# Adafruit_Trellis_4x4_3mm_HT16K33.net
KiCad netlist of a schematic drawn in EAGLE
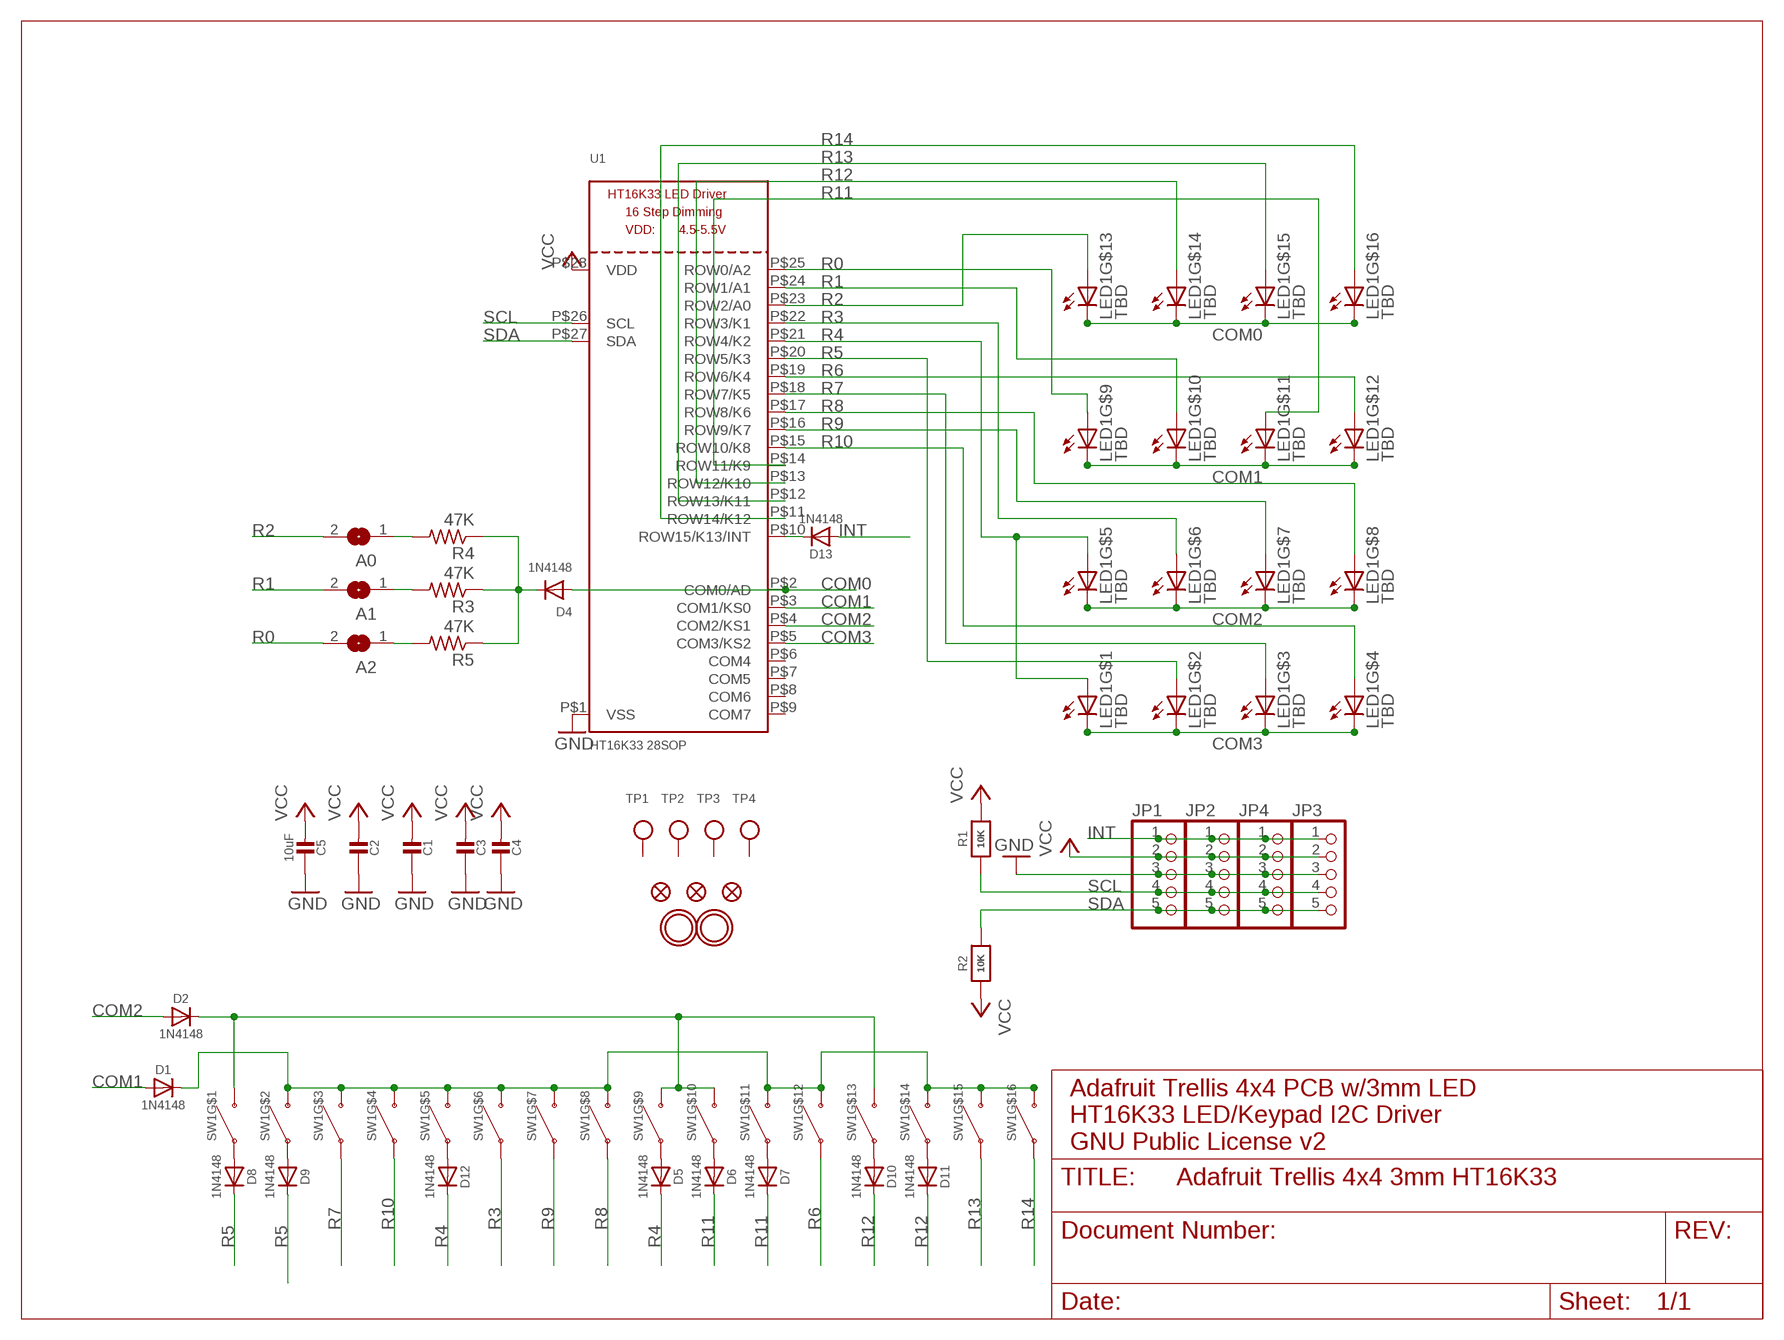
[diagram p0: schematic, sheet 1]

(export (version "E")
  (design (tool "Eeschema 10.0.6"))
  (components
    (comp (ref "A0")
      (value "SOLDERJUMPERREFLOW_NOPASTE")
      (footprint "eagle-import:SOLDERJUMPER_REFLOW_NOPASTE")
      (libsource (lib "eagle-import") (part "SOLDERJUMPERREFLOW_NOPASTE"))
    )
    (comp (ref "A1")
      (value "SOLDERJUMPERREFLOW_NOPASTE")
      (footprint "eagle-import:SOLDERJUMPER_REFLOW_NOPASTE")
      (libsource (lib "eagle-import") (part "SOLDERJUMPERREFLOW_NOPASTE"))
    )
    (comp (ref "A2")
      (value "SOLDERJUMPERREFLOW_NOPASTE")
      (footprint "eagle-import:SOLDERJUMPER_REFLOW_NOPASTE")
      (libsource (lib "eagle-import") (part "SOLDERJUMPERREFLOW_NOPASTE"))
    )
    (comp (ref "C1")
      (value "CAP_CERAMIC_0805")
      (footprint "eagle-import:_0805")
      (libsource (lib "eagle-import") (part "CAP_CERAMIC_0805"))
    )
    (comp (ref "C2")
      (value "CAP_CERAMIC_0805")
      (footprint "eagle-import:_0805")
      (libsource (lib "eagle-import") (part "CAP_CERAMIC_0805"))
    )
    (comp (ref "C3")
      (value "CAP_CERAMIC_0805")
      (footprint "eagle-import:_0805")
      (libsource (lib "eagle-import") (part "CAP_CERAMIC_0805"))
    )
    (comp (ref "C4")
      (value "CAP_CERAMIC_0805")
      (footprint "eagle-import:_0805")
      (libsource (lib "eagle-import") (part "CAP_CERAMIC_0805"))
    )
    (comp (ref "C5")
      (value "10uF")
      (footprint "eagle-import:_0805")
      (libsource (lib "eagle-import") (part "CAP_CERAMIC_0805"))
    )
    (comp (ref "D1")
      (value "1N4148")
      (footprint "eagle-import:SOD-323")
      (libsource (lib "eagle-import") (part "DIODESOD-323"))
    )
    (comp (ref "D2")
      (value "1N4148")
      (footprint "eagle-import:SOD-323")
      (libsource (lib "eagle-import") (part "DIODESOD-323"))
    )
    (comp (ref "D4")
      (value "1N4148")
      (footprint "eagle-import:SOD-323F")
      (libsource (lib "eagle-import") (part "DIODESOD-323F"))
    )
    (comp (ref "D5")
      (value "1N4148")
      (footprint "eagle-import:SOD-323")
      (libsource (lib "eagle-import") (part "DIODESOD-323"))
    )
    (comp (ref "D6")
      (value "1N4148")
      (footprint "eagle-import:SOD-323")
      (libsource (lib "eagle-import") (part "DIODESOD-323"))
    )
    (comp (ref "D7")
      (value "1N4148")
      (footprint "eagle-import:SOD-323")
      (libsource (lib "eagle-import") (part "DIODESOD-323"))
    )
    (comp (ref "D8")
      (value "1N4148")
      (footprint "eagle-import:SOD-323")
      (libsource (lib "eagle-import") (part "DIODESOD-323"))
    )
    (comp (ref "D9")
      (value "1N4148")
      (footprint "eagle-import:SOD-323")
      (libsource (lib "eagle-import") (part "DIODESOD-323"))
    )
    (comp (ref "D10")
      (value "1N4148")
      (footprint "eagle-import:SOD-323")
      (libsource (lib "eagle-import") (part "DIODESOD-323"))
    )
    (comp (ref "D11")
      (value "1N4148")
      (footprint "eagle-import:SOD-323")
      (libsource (lib "eagle-import") (part "DIODESOD-323"))
    )
    (comp (ref "D12")
      (value "1N4148")
      (footprint "eagle-import:SOD-323")
      (libsource (lib "eagle-import") (part "DIODESOD-323"))
    )
    (comp (ref "D13")
      (value "1N4148")
      (footprint "eagle-import:SOD-323")
      (libsource (lib "eagle-import") (part "DIODESOD-323"))
    )
    (comp (ref "FID1")
      (value "FIDUCIAL\"\"")
      (footprint "eagle-import:FIDUCIAL_1MM")
      (libsource (lib "eagle-import") (part "FIDUCIAL{dblquote}{dblquote}"))
    )
    (comp (ref "FID2")
      (value "FIDUCIAL\"\"")
      (footprint "eagle-import:FIDUCIAL_1MM")
      (libsource (lib "eagle-import") (part "FIDUCIAL{dblquote}{dblquote}"))
    )
    (comp (ref "FID3")
      (value "FIDUCIAL\"\"")
      (footprint "eagle-import:FIDUCIAL_1MM")
      (libsource (lib "eagle-import") (part "FIDUCIAL{dblquote}{dblquote}"))
    )
    (comp (ref "JP1")
      (value "HEADER-1X5EDGESMT")
      (footprint "eagle-import:1X5_SMT")
      (libsource (lib "eagle-import") (part "HEADER-1X5EDGESMT"))
    )
    (comp (ref "JP2")
      (value "HEADER-1X5EDGESMT")
      (footprint "eagle-import:1X5_SMT")
      (libsource (lib "eagle-import") (part "HEADER-1X5EDGESMT"))
    )
    (comp (ref "JP3")
      (value "HEADER-1X5EDGESMT")
      (footprint "eagle-import:1X5_SMT")
      (libsource (lib "eagle-import") (part "HEADER-1X5EDGESMT"))
    )
    (comp (ref "JP4")
      (value "HEADER-1X5EDGESMT")
      (footprint "eagle-import:1X5_SMT")
      (libsource (lib "eagle-import") (part "HEADER-1X5EDGESMT"))
    )
    (comp (ref "LED1")
      (value "TBD")
      (footprint "eagle-import:LED3MM-4X4GRID")
      (libsource (lib "eagle-import") (part "LED-3MM-4X4GRID-3MM"))
    )
    (comp (ref "R1")
      (value "10K")
      (footprint "eagle-import:_0805")
      (libsource (lib "eagle-import") (part "RESISTOR_0805"))
    )
    (comp (ref "R2")
      (value "10K")
      (footprint "eagle-import:_0805")
      (libsource (lib "eagle-import") (part "RESISTOR_0805"))
    )
    (comp (ref "R3")
      (value "47K")
      (footprint "eagle-import:R0805")
      (libsource (lib "eagle-import") (part "R-US_R0805"))
    )
    (comp (ref "R4")
      (value "47K")
      (footprint "eagle-import:R0805")
      (libsource (lib "eagle-import") (part "R-US_R0805"))
    )
    (comp (ref "R5")
      (value "47K")
      (footprint "eagle-import:R0805")
      (libsource (lib "eagle-import") (part "R-US_R0805"))
    )
    (comp (ref "SW1")
      (value "SWITCH-SILICON-4X4GRID-10MM-5.4MM")
      (footprint "eagle-import:ELAST_PAD_SQUARE_10MM_5.4MM_4X4GRID")
      (libsource (lib "eagle-import") (part "SWITCH-SILICON-4X4GRID-10MM-5.4MM"))
    )
    (comp (ref "TP1")
      (value "TESTPOINT")
      (footprint "eagle-import:TESTPOINT_SMT")
      (libsource (lib "eagle-import") (part "TESTPOINT"))
    )
    (comp (ref "TP2")
      (value "TESTPOINT")
      (footprint "eagle-import:TESTPOINT_SMT")
      (libsource (lib "eagle-import") (part "TESTPOINT"))
    )
    (comp (ref "TP3")
      (value "TESTPOINT")
      (footprint "eagle-import:TESTPOINT_SMT")
      (libsource (lib "eagle-import") (part "TESTPOINT"))
    )
    (comp (ref "TP4")
      (value "TESTPOINT")
      (footprint "eagle-import:TESTPOINT_SMT")
      (libsource (lib "eagle-import") (part "TESTPOINT"))
    )
    (comp (ref "U$1")
      (value "MOUNTINGHOLE2.5")
      (footprint "eagle-import:MOUNTINGHOLE_2.5_PLATED")
      (libsource (lib "eagle-import") (part "MOUNTINGHOLE2.5"))
    )
    (comp (ref "U$2")
      (value "MOUNTINGHOLE2.5")
      (footprint "eagle-import:MOUNTINGHOLE_2.5_PLATED")
      (libsource (lib "eagle-import") (part "MOUNTINGHOLE2.5"))
    )
    (comp (ref "U1")
      (value "HT16K33 28SOP")
      (footprint "eagle-import:SOP28_300MIL")
      (libsource (lib "eagle-import") (part "HT16K33_SOP28"))
    )
  )
  (nets
    (net (code "1") (name "/COM0") (class "Default")
      (node (ref "D4") (pin "A") (pinfunction "A_A") (pintype "passive"))
      (node (ref "LED1") (pin "K13") (pinfunction "C_K13") (pintype "passive"))
      (node (ref "LED1") (pin "K14") (pinfunction "C_K14") (pintype "passive"))
      (node (ref "LED1") (pin "K15") (pinfunction "C_K15") (pintype "passive"))
      (node (ref "LED1") (pin "K16") (pinfunction "C_K16") (pintype "passive"))
      (node (ref "U1") (pin "P$2") (pinfunction "COM0/AD_P$2") (pintype "bidirectional"))
    )
    (net (code "2") (name "/COM1") (class "Default")
      (node (ref "D1") (pin "A") (pinfunction "A_A") (pintype "passive"))
      (node (ref "LED1") (pin "K10") (pinfunction "C_K10") (pintype "passive"))
      (node (ref "LED1") (pin "K11") (pinfunction "C_K11") (pintype "passive"))
      (node (ref "LED1") (pin "K12") (pinfunction "C_K12") (pintype "passive"))
      (node (ref "LED1") (pin "K9") (pinfunction "C_K9") (pintype "passive"))
      (node (ref "U1") (pin "P$3") (pinfunction "COM1/KS0_P$3") (pintype "bidirectional"))
    )
    (net (code "3") (name "/COM2") (class "Default")
      (node (ref "D2") (pin "A") (pinfunction "A_A") (pintype "passive"))
      (node (ref "LED1") (pin "K5") (pinfunction "C_K5") (pintype "passive"))
      (node (ref "LED1") (pin "K6") (pinfunction "C_K6") (pintype "passive"))
      (node (ref "LED1") (pin "K7") (pinfunction "C_K7") (pintype "passive"))
      (node (ref "LED1") (pin "K8") (pinfunction "C_K8") (pintype "passive"))
      (node (ref "U1") (pin "P$4") (pinfunction "COM2/KS1_P$4") (pintype "bidirectional"))
    )
    (net (code "4") (name "/COM3") (class "Default")
      (node (ref "LED1") (pin "K1") (pinfunction "C_K1") (pintype "passive"))
      (node (ref "LED1") (pin "K2") (pinfunction "C_K2") (pintype "passive"))
      (node (ref "LED1") (pin "K3") (pinfunction "C_K3") (pintype "passive"))
      (node (ref "LED1") (pin "K4") (pinfunction "C_K4") (pintype "passive"))
      (node (ref "U1") (pin "P$5") (pinfunction "COM3/KS2_P$5") (pintype "bidirectional"))
    )
    (net (code "5") (name "/INT") (class "Default")
      (node (ref "D13") (pin "A") (pinfunction "A_A") (pintype "passive"))
      (node (ref "JP1") (pin "1") (pinfunction "1_1") (pintype "passive"))
      (node (ref "JP2") (pin "1") (pinfunction "1_1") (pintype "passive"))
      (node (ref "JP3") (pin "1") (pinfunction "1_1") (pintype "passive"))
      (node (ref "JP4") (pin "1") (pinfunction "1_1") (pintype "passive"))
    )
    (net (code "6") (name "/R0") (class "Default")
      (node (ref "A2") (pin "2") (pinfunction "2_2") (pintype "passive"))
      (node (ref "LED1") (pin "A9") (pinfunction "A_A9") (pintype "passive"))
      (node (ref "U1") (pin "P$25") (pinfunction "ROW0/A2_P$25") (pintype "bidirectional"))
    )
    (net (code "7") (name "/R1") (class "Default")
      (node (ref "A1") (pin "2") (pinfunction "2_2") (pintype "passive"))
      (node (ref "LED1") (pin "A10") (pinfunction "A_A10") (pintype "passive"))
      (node (ref "U1") (pin "P$24") (pinfunction "ROW1/A1_P$24") (pintype "bidirectional"))
    )
    (net (code "8") (name "/R2") (class "Default")
      (node (ref "A0") (pin "2") (pinfunction "2_2") (pintype "passive"))
      (node (ref "LED1") (pin "A13") (pinfunction "A_A13") (pintype "passive"))
      (node (ref "U1") (pin "P$23") (pinfunction "ROW2/A0_P$23") (pintype "bidirectional"))
    )
    (net (code "9") (name "/R3") (class "Default")
      (node (ref "LED1") (pin "A6") (pinfunction "A_A6") (pintype "passive"))
      (node (ref "SW1") (pin "A6") (pinfunction "P$1_A6") (pintype "bidirectional"))
      (node (ref "U1") (pin "P$22") (pinfunction "ROW3/K1_P$22") (pintype "bidirectional"))
    )
    (net (code "10") (name "/R4") (class "Default")
      (node (ref "D12") (pin "C") (pinfunction "C_C") (pintype "passive"))
      (node (ref "D5") (pin "C") (pinfunction "C_C") (pintype "passive"))
      (node (ref "LED1") (pin "A1") (pinfunction "A_A1") (pintype "passive"))
      (node (ref "LED1") (pin "A5") (pinfunction "A_A5") (pintype "passive"))
      (node (ref "U1") (pin "P$21") (pinfunction "ROW4/K2_P$21") (pintype "bidirectional"))
    )
    (net (code "11") (name "/R5") (class "Default")
      (node (ref "D8") (pin "C") (pinfunction "C_C") (pintype "passive"))
      (node (ref "D9") (pin "C") (pinfunction "C_C") (pintype "passive"))
      (node (ref "LED1") (pin "A2") (pinfunction "A_A2") (pintype "passive"))
      (node (ref "U1") (pin "P$20") (pinfunction "ROW5/K3_P$20") (pintype "bidirectional"))
    )
    (net (code "12") (name "/R6") (class "Default")
      (node (ref "LED1") (pin "A12") (pinfunction "A_A12") (pintype "passive"))
      (node (ref "SW1") (pin "A12") (pinfunction "P$1_A12") (pintype "bidirectional"))
      (node (ref "U1") (pin "P$19") (pinfunction "ROW6/K4_P$19") (pintype "bidirectional"))
    )
    (net (code "13") (name "/R7") (class "Default")
      (node (ref "LED1") (pin "A3") (pinfunction "A_A3") (pintype "passive"))
      (node (ref "SW1") (pin "A3") (pinfunction "P$1_A3") (pintype "bidirectional"))
      (node (ref "U1") (pin "P$18") (pinfunction "ROW7/K5_P$18") (pintype "bidirectional"))
    )
    (net (code "14") (name "/R8") (class "Default")
      (node (ref "LED1") (pin "A8") (pinfunction "A_A8") (pintype "passive"))
      (node (ref "SW1") (pin "A8") (pinfunction "P$1_A8") (pintype "bidirectional"))
      (node (ref "U1") (pin "P$17") (pinfunction "ROW8/K6_P$17") (pintype "bidirectional"))
    )
    (net (code "15") (name "/R9") (class "Default")
      (node (ref "LED1") (pin "A7") (pinfunction "A_A7") (pintype "passive"))
      (node (ref "SW1") (pin "A7") (pinfunction "P$1_A7") (pintype "bidirectional"))
      (node (ref "U1") (pin "P$16") (pinfunction "ROW9/K7_P$16") (pintype "bidirectional"))
    )
    (net (code "16") (name "/R10") (class "Default")
      (node (ref "LED1") (pin "A4") (pinfunction "A_A4") (pintype "passive"))
      (node (ref "SW1") (pin "A4") (pinfunction "P$1_A4") (pintype "bidirectional"))
      (node (ref "U1") (pin "P$15") (pinfunction "ROW10/K8_P$15") (pintype "bidirectional"))
    )
    (net (code "17") (name "/R11") (class "Default")
      (node (ref "D6") (pin "C") (pinfunction "C_C") (pintype "passive"))
      (node (ref "D7") (pin "C") (pinfunction "C_C") (pintype "passive"))
      (node (ref "LED1") (pin "A11") (pinfunction "A_A11") (pintype "passive"))
      (node (ref "U1") (pin "P$14") (pinfunction "ROW11/K9_P$14") (pintype "bidirectional"))
    )
    (net (code "18") (name "/R12") (class "Default")
      (node (ref "D10") (pin "C") (pinfunction "C_C") (pintype "passive"))
      (node (ref "D11") (pin "C") (pinfunction "C_C") (pintype "passive"))
      (node (ref "LED1") (pin "A14") (pinfunction "A_A14") (pintype "passive"))
      (node (ref "U1") (pin "P$13") (pinfunction "ROW12/K10_P$13") (pintype "bidirectional"))
    )
    (net (code "19") (name "/R13") (class "Default")
      (node (ref "LED1") (pin "A15") (pinfunction "A_A15") (pintype "passive"))
      (node (ref "SW1") (pin "A15") (pinfunction "P$1_A15") (pintype "bidirectional"))
      (node (ref "U1") (pin "P$12") (pinfunction "ROW13/K11_P$12") (pintype "bidirectional"))
    )
    (net (code "20") (name "/R14") (class "Default")
      (node (ref "LED1") (pin "A16") (pinfunction "A_A16") (pintype "passive"))
      (node (ref "SW1") (pin "A16") (pinfunction "P$1_A16") (pintype "bidirectional"))
      (node (ref "U1") (pin "P$11") (pinfunction "ROW14/K12_P$11") (pintype "bidirectional"))
    )
    (net (code "21") (name "/SCL") (class "Default")
      (node (ref "JP1") (pin "4") (pinfunction "4_4") (pintype "passive"))
      (node (ref "JP2") (pin "4") (pinfunction "4_4") (pintype "passive"))
      (node (ref "JP3") (pin "4") (pinfunction "4_4") (pintype "passive"))
      (node (ref "JP4") (pin "4") (pinfunction "4_4") (pintype "passive"))
      (node (ref "R1") (pin "1") (pinfunction "1_1") (pintype "passive"))
      (node (ref "U1") (pin "P$26") (pinfunction "SCL_P$26") (pintype "bidirectional"))
    )
    (net (code "22") (name "/SDA") (class "Default")
      (node (ref "JP1") (pin "5") (pinfunction "5_5") (pintype "passive"))
      (node (ref "JP2") (pin "5") (pinfunction "5_5") (pintype "passive"))
      (node (ref "JP3") (pin "5") (pinfunction "5_5") (pintype "passive"))
      (node (ref "JP4") (pin "5") (pinfunction "5_5") (pintype "passive"))
      (node (ref "R2") (pin "2") (pinfunction "2_2") (pintype "passive"))
      (node (ref "U1") (pin "P$27") (pinfunction "SDA_P$27") (pintype "bidirectional"))
    )
    (net (code "23") (name "GND") (class "Default")
      (node (ref "C1") (pin "1") (pinfunction "1_1") (pintype "passive"))
      (node (ref "C2") (pin "1") (pinfunction "1_1") (pintype "passive"))
      (node (ref "C3") (pin "1") (pinfunction "1_1") (pintype "passive"))
      (node (ref "C4") (pin "1") (pinfunction "1_1") (pintype "passive"))
      (node (ref "C5") (pin "1") (pinfunction "1_1") (pintype "passive"))
      (node (ref "JP1") (pin "3") (pinfunction "3_3") (pintype "passive"))
      (node (ref "JP2") (pin "3") (pinfunction "3_3") (pintype "passive"))
      (node (ref "JP3") (pin "3") (pinfunction "3_3") (pintype "passive"))
      (node (ref "JP4") (pin "3") (pinfunction "3_3") (pintype "passive"))
      (node (ref "U1") (pin "P$1") (pinfunction "VSS_P$1") (pintype "bidirectional"))
    )
    (net (code "24") (name "Net-(A0-Pad1)") (class "Default")
      (node (ref "A0") (pin "1") (pinfunction "1_1") (pintype "passive"))
      (node (ref "R4") (pin "2") (pinfunction "2_2") (pintype "passive"))
    )
    (net (code "25") (name "Net-(A1-Pad1)") (class "Default")
      (node (ref "A1") (pin "1") (pinfunction "1_1") (pintype "passive"))
      (node (ref "R3") (pin "2") (pinfunction "2_2") (pintype "passive"))
    )
    (net (code "26") (name "Net-(A2-Pad1)") (class "Default")
      (node (ref "A2") (pin "1") (pinfunction "1_1") (pintype "passive"))
      (node (ref "R5") (pin "2") (pinfunction "2_2") (pintype "passive"))
    )
    (net (code "27") (name "Net-(D4-PadC)") (class "Default")
      (node (ref "D4") (pin "C") (pinfunction "C_C") (pintype "passive"))
      (node (ref "R3") (pin "1") (pinfunction "1_1") (pintype "passive"))
      (node (ref "R4") (pin "1") (pinfunction "1_1") (pintype "passive"))
      (node (ref "R5") (pin "1") (pinfunction "1_1") (pintype "passive"))
    )
    (net (code "28") (name "Net-(SW1A-P$1)") (class "Default")
      (node (ref "D8") (pin "A") (pinfunction "A_A") (pintype "passive"))
      (node (ref "SW1") (pin "A1") (pinfunction "P$1_A1") (pintype "bidirectional"))
    )
    (net (code "29") (name "Net-(SW1A-P$2)") (class "Default")
      (node (ref "D2") (pin "C") (pinfunction "C_C") (pintype "passive"))
      (node (ref "SW1") (pin "B1") (pinfunction "P$2_B1") (pintype "bidirectional"))
      (node (ref "SW1") (pin "B10") (pinfunction "P$2_B10") (pintype "bidirectional"))
      (node (ref "SW1") (pin "B13") (pinfunction "P$2_B13") (pintype "bidirectional"))
      (node (ref "SW1") (pin "B9") (pinfunction "P$2_B9") (pintype "bidirectional"))
    )
    (net (code "30") (name "Net-(SW1B-P$1)") (class "Default")
      (node (ref "D6") (pin "A") (pinfunction "A_A") (pintype "passive"))
      (node (ref "SW1") (pin "A10") (pinfunction "P$1_A10") (pintype "bidirectional"))
    )
    (net (code "31") (name "Net-(SW1C-P$1)") (class "Default")
      (node (ref "D7") (pin "A") (pinfunction "A_A") (pintype "passive"))
      (node (ref "SW1") (pin "A11") (pinfunction "P$1_A11") (pintype "bidirectional"))
    )
    (net (code "32") (name "Net-(SW1C-P$2)") (class "Default")
      (node (ref "D1") (pin "C") (pinfunction "C_C") (pintype "passive"))
      (node (ref "SW1") (pin "B11") (pinfunction "P$2_B11") (pintype "bidirectional"))
      (node (ref "SW1") (pin "B12") (pinfunction "P$2_B12") (pintype "bidirectional"))
      (node (ref "SW1") (pin "B14") (pinfunction "P$2_B14") (pintype "bidirectional"))
      (node (ref "SW1") (pin "B15") (pinfunction "P$2_B15") (pintype "bidirectional"))
      (node (ref "SW1") (pin "B16") (pinfunction "P$2_B16") (pintype "bidirectional"))
      (node (ref "SW1") (pin "B2") (pinfunction "P$2_B2") (pintype "bidirectional"))
      (node (ref "SW1") (pin "B3") (pinfunction "P$2_B3") (pintype "bidirectional"))
      (node (ref "SW1") (pin "B4") (pinfunction "P$2_B4") (pintype "bidirectional"))
      (node (ref "SW1") (pin "B5") (pinfunction "P$2_B5") (pintype "bidirectional"))
      (node (ref "SW1") (pin "B6") (pinfunction "P$2_B6") (pintype "bidirectional"))
      (node (ref "SW1") (pin "B7") (pinfunction "P$2_B7") (pintype "bidirectional"))
      (node (ref "SW1") (pin "B8") (pinfunction "P$2_B8") (pintype "bidirectional"))
    )
    (net (code "33") (name "Net-(SW1E-P$1)") (class "Default")
      (node (ref "D10") (pin "A") (pinfunction "A_A") (pintype "passive"))
      (node (ref "SW1") (pin "A13") (pinfunction "P$1_A13") (pintype "bidirectional"))
    )
    (net (code "34") (name "Net-(SW1F-P$1)") (class "Default")
      (node (ref "D11") (pin "A") (pinfunction "A_A") (pintype "passive"))
      (node (ref "SW1") (pin "A14") (pinfunction "P$1_A14") (pintype "bidirectional"))
    )
    (net (code "35") (name "Net-(SW1I-P$1)") (class "Default")
      (node (ref "D9") (pin "A") (pinfunction "A_A") (pintype "passive"))
      (node (ref "SW1") (pin "A2") (pinfunction "P$1_A2") (pintype "bidirectional"))
    )
    (net (code "36") (name "Net-(SW1L-P$1)") (class "Default")
      (node (ref "D12") (pin "A") (pinfunction "A_A") (pintype "passive"))
      (node (ref "SW1") (pin "A5") (pinfunction "P$1_A5") (pintype "bidirectional"))
    )
    (net (code "37") (name "Net-(SW1P-P$1)") (class "Default")
      (node (ref "D5") (pin "A") (pinfunction "A_A") (pintype "passive"))
      (node (ref "SW1") (pin "A9") (pinfunction "P$1_A9") (pintype "bidirectional"))
    )
    (net (code "38") (name "Net-(U1-ROW15{slash}K13{slash}INT)") (class "Default")
      (node (ref "D13") (pin "C") (pinfunction "C_C") (pintype "passive"))
      (node (ref "U1") (pin "P$10") (pinfunction "ROW15/K13/INT_P$10") (pintype "bidirectional"))
    )
    (net (code "39") (name "VCC") (class "Default")
      (node (ref "C1") (pin "2") (pinfunction "2_2") (pintype "passive"))
      (node (ref "C2") (pin "2") (pinfunction "2_2") (pintype "passive"))
      (node (ref "C3") (pin "2") (pinfunction "2_2") (pintype "passive"))
      (node (ref "C4") (pin "2") (pinfunction "2_2") (pintype "passive"))
      (node (ref "C5") (pin "2") (pinfunction "2_2") (pintype "passive"))
      (node (ref "JP1") (pin "2") (pinfunction "2_2") (pintype "passive"))
      (node (ref "JP2") (pin "2") (pinfunction "2_2") (pintype "passive"))
      (node (ref "JP3") (pin "2") (pinfunction "2_2") (pintype "passive"))
      (node (ref "JP4") (pin "2") (pinfunction "2_2") (pintype "passive"))
      (node (ref "R1") (pin "2") (pinfunction "2_2") (pintype "passive"))
      (node (ref "R2") (pin "1") (pinfunction "1_1") (pintype "passive"))
      (node (ref "U1") (pin "P$28") (pinfunction "VDD_P$28") (pintype "bidirectional"))
    )
    (net (code "40") (name "unconnected-(TP1-PadP$1)") (class "Default")
      (node (ref "TP1") (pin "P$1") (pinfunction "P$1_P$1") (pintype "bidirectional"))
    )
    (net (code "41") (name "unconnected-(TP2-PadP$1)") (class "Default")
      (node (ref "TP2") (pin "P$1") (pinfunction "P$1_P$1") (pintype "bidirectional"))
    )
    (net (code "42") (name "unconnected-(TP3-PadP$1)") (class "Default")
      (node (ref "TP3") (pin "P$1") (pinfunction "P$1_P$1") (pintype "bidirectional"))
    )
    (net (code "43") (name "unconnected-(TP4-PadP$1)") (class "Default")
      (node (ref "TP4") (pin "P$1") (pinfunction "P$1_P$1") (pintype "bidirectional"))
    )
    (net (code "44") (name "unconnected-(U1-COM4-PadP$6)") (class "Default")
      (node (ref "U1") (pin "P$6") (pinfunction "COM4_P$6") (pintype "bidirectional"))
    )
    (net (code "45") (name "unconnected-(U1-COM5-PadP$7)") (class "Default")
      (node (ref "U1") (pin "P$7") (pinfunction "COM5_P$7") (pintype "bidirectional"))
    )
    (net (code "46") (name "unconnected-(U1-COM6-PadP$8)") (class "Default")
      (node (ref "U1") (pin "P$8") (pinfunction "COM6_P$8") (pintype "bidirectional"))
    )
    (net (code "47") (name "unconnected-(U1-COM7-PadP$9)") (class "Default")
      (node (ref "U1") (pin "P$9") (pinfunction "COM7_P$9") (pintype "bidirectional"))
    )
  )
)
